# PEAK_LCW_1.net
KiCad netlist of a schematic drawn in Altium Designer
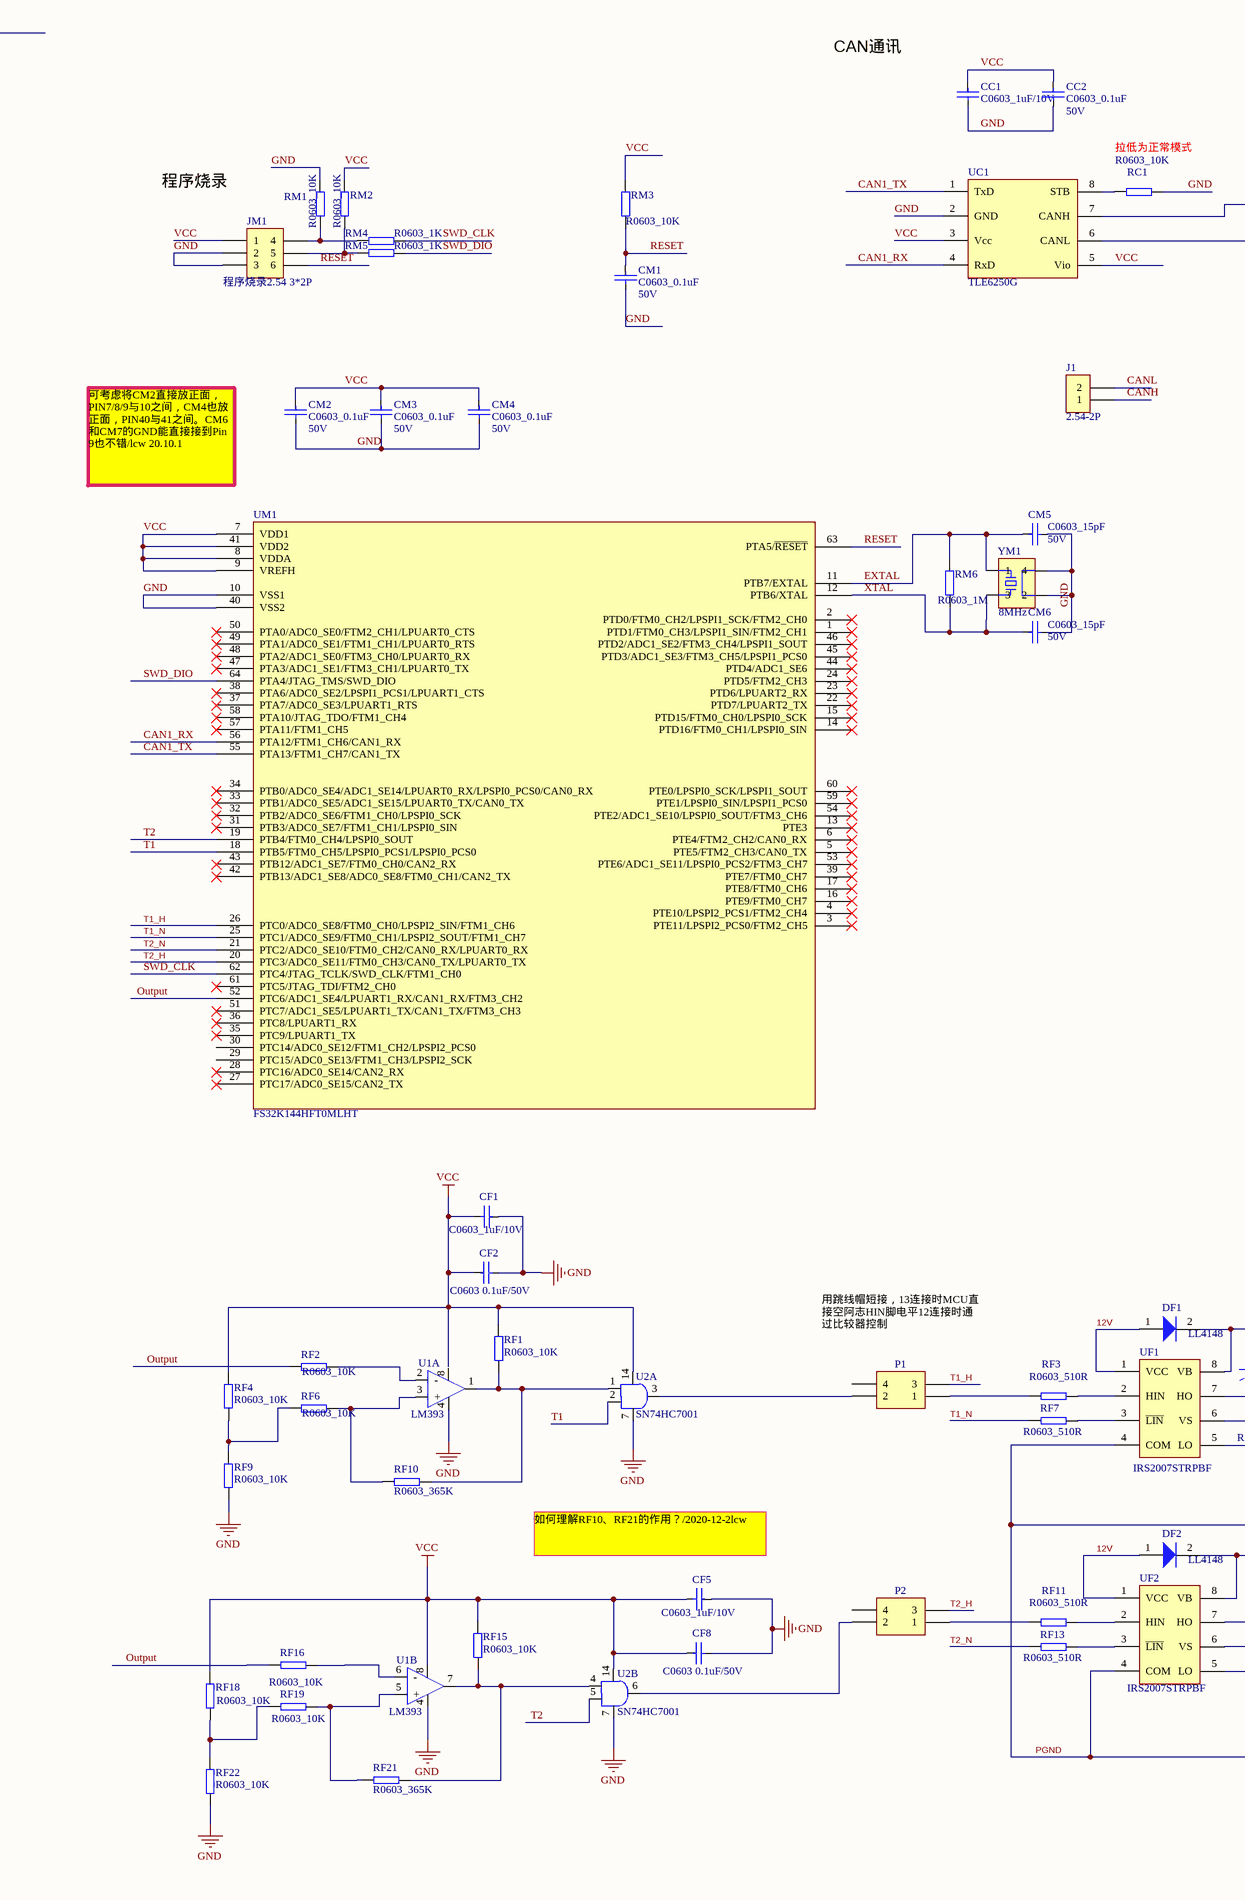
[diagram p0: PEAK——LCW (1).SchDoc, left]
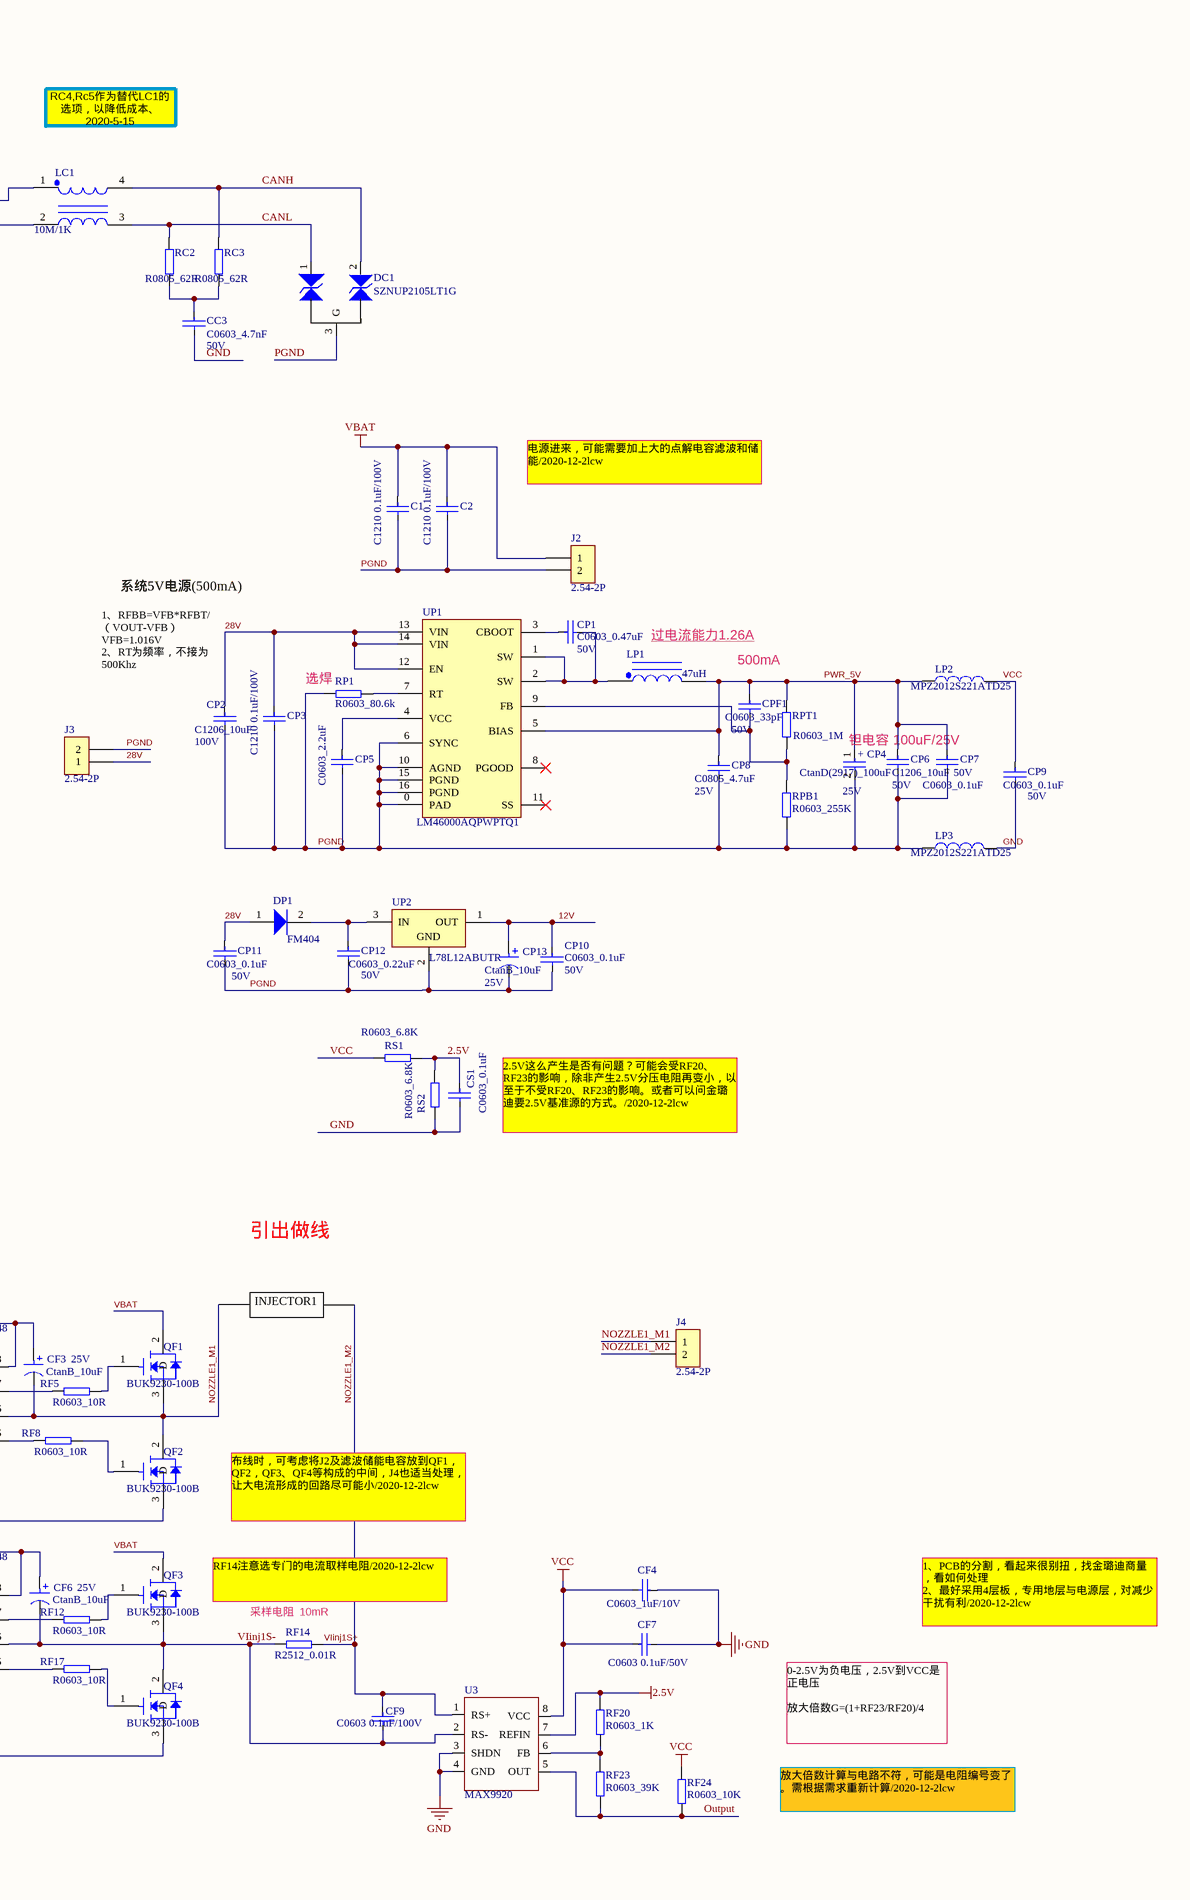
[diagram p1: PEAK——LCW (1).SchDoc, right]

(export (version "E")
  (design (tool "Eeschema 10.0.6"))
  (components
    (comp (ref "C1")
      (value "C1210 0.1uF/100V")
      (footprint "C1210")
      (description "C1210 0.1uF/50V 10%")
      (fields (field (name "VOLTAGE") "100V") (field (name "PART NUMBER") "3170014005"))
      (libsource (lib "BMSer") (part "CAP"))
    )
    (comp (ref "C2")
      (value "C1210 0.1uF/100V")
      (footprint "C1210")
      (description "C1210 0.1uF/50V 10%")
      (fields (field (name "VOLTAGE") "100V") (field (name "PART NUMBER") "3170014005"))
      (libsource (lib "BMSer") (part "CAP"))
    )
    (comp (ref "CC1")
      (value "C0603_1uF/10V")
      (footprint "C0603")
      (description "C0603 0.1uF/50V 10%")
      (fields (field (name "VOLTAGE") "10V") (field (name "PART NUMBER") "3170011015"))
      (libsource (lib "BMSer") (part "CAP"))
    )
    (comp (ref "CC2")
      (value "C0603_0.1uF")
      (footprint "C0603")
      (description "C0603 0.1uF/50V 10%")
      (fields
        (field (name "VOLTAGE") "50V")
        (field (name "PART NUMBER") "3170011015")
        (field (name "MANUFACTURER") "YAGEO")
      )
      (libsource (lib "BMSer") (part "CAP"))
    )
    (comp (ref "CC3")
      (value "C0603_4.7nF")
      (footprint "C0603")
      (description "C0603 4.7nF/50V 5% X7R")
      (fields
        (field (name "VOLTAGE") "50V")
        (field (name "PART NUMBER") "3170011009")
        (field (name "MANUFACTURER") "YAGEO")
      )
      (libsource (lib "BMSer") (part "CAP"))
    )
    (comp (ref "CF1")
      (value "C0603_1uF/10V")
      (footprint "C0603")
      (description "C0603 0.1uF/50V 10%")
      (fields (field (name "VOLTAGE") "10V") (field (name "PART NUMBER") "3170011015"))
      (libsource (lib "BMSer") (part "CAP"))
    )
    (comp (ref "CF2")
      (value "C0603 0.1uF/50V")
      (footprint "C0603")
      (description "C0603 0.1uF/50V 10%")
      (fields (field (name "VOLTAGE") "50V") (field (name "PART NUMBER") "3170011015"))
      (libsource (lib "BMSer") (part "CAP"))
    )
    (comp (ref "CF3")
      (value "CtanB_10uF")
      (footprint "CTANB")
      (description "CtanB(1210) 10uF/25V 10%")
      (fields
        (field (name "PART NUMBER") "3172690034")
        (field (name "MANUFACTURER") "AVX")
        (field (name "VOLTAGE") "25V")
      )
      (libsource (lib "BMSer") (part "CAP_T"))
    )
    (comp (ref "CF4")
      (value "C0603_1uF/10V")
      (footprint "C0603")
      (description "C0603 0.1uF/50V 10%")
      (fields (field (name "VOLTAGE") "10V") (field (name "PART NUMBER") "3170011015"))
      (libsource (lib "BMSer") (part "CAP"))
    )
    (comp (ref "CF5")
      (value "C0603_1uF/10V")
      (footprint "C0603")
      (description "C0603 0.1uF/50V 10%")
      (fields (field (name "VOLTAGE") "10V") (field (name "PART NUMBER") "3170011015"))
      (libsource (lib "BMSer") (part "CAP"))
    )
    (comp (ref "CF6")
      (value "CtanB_10uF")
      (footprint "CTANB")
      (description "CtanB(1210) 10uF/25V 10%")
      (fields
        (field (name "PART NUMBER") "3172690034")
        (field (name "MANUFACTURER") "AVX")
        (field (name "VOLTAGE") "25V")
      )
      (libsource (lib "BMSer") (part "CAP_T"))
    )
    (comp (ref "CF7")
      (value "C0603 0.1uF/50V")
      (footprint "C0603")
      (description "C0603 0.1uF/50V 10%")
      (fields (field (name "VOLTAGE") "50V") (field (name "PART NUMBER") "3170011015"))
      (libsource (lib "BMSer") (part "CAP"))
    )
    (comp (ref "CF8")
      (value "C0603 0.1uF/50V")
      (footprint "C0603")
      (description "C0603 0.1uF/50V 10%")
      (fields (field (name "VOLTAGE") "50V") (field (name "PART NUMBER") "3170011015"))
      (libsource (lib "BMSer") (part "CAP"))
    )
    (comp (ref "CF9")
      (value "C0603 0.1uF/100V")
      (footprint "C0603")
      (description "C0603 0.1uF/50V 10%")
      (fields (field (name "VOLTAGE") "50V") (field (name "PART NUMBER") "3170011015"))
      (libsource (lib "BMSer") (part "CAP"))
    )
    (comp (ref "CM1")
      (value "C0603_0.1uF")
      (footprint "C0603")
      (description "C0603 0.1uF/50V 10%")
      (fields
        (field (name "VOLTAGE") "50V")
        (field (name "PART NUMBER") "3170011015")
        (field (name "MANUFACTURER") "YAGEO")
      )
      (libsource (lib "BMSer") (part "CAP"))
    )
    (comp (ref "CM2")
      (value "C0603_0.1uF")
      (footprint "C0603")
      (description "C0603 0.1uF/50V 10%")
      (fields
        (field (name "VOLTAGE") "50V")
        (field (name "PART NUMBER") "3170011015")
        (field (name "MANUFACTURER") "YAGEO")
      )
      (libsource (lib "BMSer") (part "CAP"))
    )
    (comp (ref "CM3")
      (value "C0603_0.1uF")
      (footprint "C0603")
      (description "C0603 0.1uF/50V 10%")
      (fields
        (field (name "VOLTAGE") "50V")
        (field (name "PART NUMBER") "3170011015")
        (field (name "MANUFACTURER") "YAGEO")
      )
      (libsource (lib "BMSer") (part "CAP"))
    )
    (comp (ref "CM4")
      (value "C0603_0.1uF")
      (footprint "C0603")
      (description "C0603 0.1uF/50V 10%")
      (fields
        (field (name "VOLTAGE") "50V")
        (field (name "PART NUMBER") "3170011015")
        (field (name "MANUFACTURER") "YAGEO")
      )
      (libsource (lib "BMSer") (part "CAP"))
    )
    (comp (ref "CM5")
      (value "C0603_15pF")
      (footprint "C0603")
      (description "C0603 15pF/50V 10%")
      (fields
        (field (name "VOLTAGE") "50V")
        (field (name "PART NUMBER") "3172510040")
        (field (name "MANUFACTURER") "YAGEO")
      )
      (libsource (lib "BMSer") (part "CAP"))
    )
    (comp (ref "CM6")
      (value "C0603_15pF")
      (footprint "C0603")
      (description "C0603 15pF/50V 10%")
      (fields
        (field (name "VOLTAGE") "50V")
        (field (name "PART NUMBER") "3172510040")
        (field (name "MANUFACTURER") "YAGEO")
      )
      (libsource (lib "BMSer") (part "CAP"))
    )
    (comp (ref "CP1")
      (value "C0603_0.47uF")
      (footprint "C0603")
      (description "C0603 0.47uF/50V 10%")
      (fields
        (field (name "VOLTAGE") "50V")
        (field (name "PART NUMBER") "3170011017")
        (field (name "MANUFACTURER") "murata")
      )
      (libsource (lib "BMSer") (part "CAP"))
    )
    (comp (ref "CP2")
      (value "C1206_10uF")
      (footprint "C1206")
      (description "C1206 10uF/50V  10%")
      (fields
        (field (name "VOLTAGE") "100V")
        (field (name "PART NUMBER") "3172530019")
        (field (name "MANUFACTURER") "YAGEO")
      )
      (libsource (lib "BMSer") (part "CAP"))
    )
    (comp (ref "CP3")
      (value "C1210 0.1uF/100V")
      (footprint "C1210")
      (description "C1210 0.1uF/100V 10%")
      (fields (field (name "VOLTAGE") "100V") (field (name "PART NUMBER") "3170014005"))
      (libsource (lib "BMSer") (part "CAP"))
    )
    (comp (ref "CP4")
      (value "CtanD(2917)_100uF")
      (footprint "CTAND")
      (description "CtanD(2917) 100uF/25V 10%")
      (fields
        (field (name "VOLTAGE") "25V")
        (field (name "PART NUMBER") "3170030004")
        (field (name "MANUFACTURER") "AVX")
      )
      (libsource (lib "BMSer") (part "CAP_E"))
    )
    (comp (ref "CP5")
      (value "C0603_2.2uF")
      (footprint "C0603")
      (description "C0603 2.2uF/50V 10%")
      (fields (field (name "VOLTAGE") "50V") (field (name "PART NUMBER") "3170011030"))
      (libsource (lib "BMSer") (part "CAP"))
    )
    (comp (ref "CP6")
      (value "C1206_10uF")
      (footprint "C1206")
      (description "C1206 10uF/50V  10%")
      (fields
        (field (name "VOLTAGE") "50V")
        (field (name "PART NUMBER") "3172530019")
        (field (name "MANUFACTURER") "YAGEO")
      )
      (libsource (lib "BMSer") (part "CAP"))
    )
    (comp (ref "CP7")
      (value "C0603_0.1uF")
      (footprint "C0603")
      (description "C0603 0.1uF/50V 10%")
      (fields
        (field (name "VOLTAGE") "50V")
        (field (name "PART NUMBER") "3170011015")
        (field (name "MANUFACTURER") "YAGEO")
      )
      (libsource (lib "BMSer") (part "CAP"))
    )
    (comp (ref "CP8")
      (value "C0805_4.7uF")
      (footprint "C0805")
      (description "C0805 4.7uF/25V 10%")
      (fields
        (field (name "VOLTAGE") "25V")
        (field (name "PART NUMBER") "3170012010")
        (field (name "MANUFACTURER") "YAGEO")
      )
      (libsource (lib "BMSer") (part "CAP"))
    )
    (comp (ref "CP9")
      (value "C0603_0.1uF")
      (footprint "C0603")
      (description "C0603 0.1uF/50V 10%")
      (fields
        (field (name "VOLTAGE") "50V")
        (field (name "PART NUMBER") "3170011015")
        (field (name "MANUFACTURER") "YAGEO")
      )
      (libsource (lib "BMSer") (part "CAP"))
    )
    (comp (ref "CP10")
      (value "C0603_0.1uF")
      (footprint "C0603")
      (description "C0603 0.1uF/50V 10%  X7R")
      (fields
        (field (name "VOLTAGE") "50V")
        (field (name "PART NUMBER") "3170011015")
        (field (name "MANUFACTURER") "YAGEO")
      )
      (libsource (lib "BMSer") (part "CAP"))
    )
    (comp (ref "CP11")
      (value "C0603_0.1uF")
      (footprint "C0603")
      (description "C0603 0.1uF/50V 10%")
      (fields
        (field (name "VOLTAGE") "50V")
        (field (name "PART NUMBER") "3170011015")
        (field (name "MANUFACTURER") "YAGEO")
      )
      (libsource (lib "BMSer") (part "CAP"))
    )
    (comp (ref "CP12")
      (value "C0603_0.22uF")
      (footprint "C0603")
      (description "C0603 0.22uF/50V 10%")
      (fields
        (field (name "VOLTAGE") "50V")
        (field (name "PART NUMBER") "3172510028")
        (field (name "MANUFACTURER") "YAGEO")
      )
      (libsource (lib "BMSer") (part "CAP"))
    )
    (comp (ref "CP13")
      (value "CtanB_10uF")
      (footprint "CTANB")
      (description "CtanB(1210) 10uF/25V 10%")
      (fields
        (field (name "PART NUMBER") "3172690034")
        (field (name "MANUFACTURER") "AVX")
        (field (name "VOLTAGE") "25V")
      )
      (libsource (lib "BMSer") (part "CAP_T"))
    )
    (comp (ref "CPF1")
      (value "C0603_33pF")
      (footprint "C0603")
      (description "C0603 33pF/50V 10%")
      (fields
        (field (name "VOLTAGE") "50V")
        (field (name "PART NUMBER") "3172510041")
        (field (name "MANUFACTURER") "YAGEO")
      )
      (libsource (lib "BMSer") (part "CAP"))
    )
    (comp (ref "CS1")
      (value "C0603_0.1uF")
      (footprint "C0603")
      (description "C0603 0.1uF/50V 10%")
      (fields (field (name "VOLTAGE") "50V") (field (name "PART NUMBER") "3170011015"))
      (libsource (lib "BMSer") (part "CAP"))
    )
    (comp (ref "DC1")
      (value "SZNUP2105LT1G")
      (footprint "SOT-23")
      (description "SOT-23 SZNUP2105LT1G")
      (fields (field (name "PART NUMBER") "3110050073") (field (name "MANUFACTURER") "ON"))
      (libsource (lib "BMSer") (part "SZNUP2105LT1G"))
    )
    (comp (ref "DF1")
      (value "LL4148")
      (footprint "SOD-80")
      (description "SOD-80  LL4148 2A/75V")
      (fields (field (name "PART NUMBER") "3110010015") (field (name "MANUFACTURER") "VISHA"))
      (libsource (lib "BMSer") (part "DIODE"))
    )
    (comp (ref "DF2")
      (value "LL4148")
      (footprint "SOD-80")
      (description "SOD-80  LL4148 2A/75V")
      (fields (field (name "PART NUMBER") "3110010015") (field (name "MANUFACTURER") "VISHA"))
      (libsource (lib "BMSer") (part "DIODE"))
    )
    (comp (ref "DP1")
      (value "FM404")
      (footprint "D0-214AC")
      (description "D0-214AC FM404")
      (fields (field (name "PART NUMBER") "13110010013") (field (name "MANUFACTURER") "LRC"))
      (libsource (lib "BMSer") (part "DIODE"))
    )
    (comp (ref "J1")
      (value "2.54-2P")
      (footprint "2.54-2P")
      (fields (field (name "PART NUMBER") "53190010200"))
      (libsource (lib "BMSer") (part "CON2"))
    )
    (comp (ref "J2")
      (value "2.54-2P")
      (footprint "2.54-2P")
      (fields (field (name "PART NUMBER") "53190010200"))
      (libsource (lib "") (part "CON2_1"))
    )
    (comp (ref "J3")
      (value "2.54-2P")
      (footprint "2.54-2P")
      (fields (field (name "PART NUMBER") "53190010200"))
      (libsource (lib "BMSer") (part "CON2"))
    )
    (comp (ref "J4")
      (value "2.54-2P")
      (footprint "2.54-2P")
      (fields (field (name "PART NUMBER") "53190010200"))
      (libsource (lib "") (part "CON2_1"))
    )
    (comp (ref "JM1")
      (value "程序烧录2.54 3*2P")
      (footprint "3x2P")
      (fields (field (name "PART NUMBER") "53190010221"))
      (libsource (lib "BMSer") (part "CON3x2"))
    )
    (comp (ref "LC1")
      (value "10M/1K")
      (footprint "ACT45B")
      (description "ACT45B-510-2P-TL  10M/1K/0.2A")
      (fields (field (name "PART NUMBER") "3180020022") (field (name "MANUFACTURER") "TDK"))
      (libsource (lib "BMSer") (part "INDUCTOR3"))
    )
    (comp (ref "LP1")
      (value "47uH")
      (footprint "LGK")
      (description "CLF7045NIT-470M-D  47uH/1.26A  Q")
      (fields (field (name "PART NUMBER") "53180020033") (field (name "MANUFACTURER") "TDK"))
      (libsource (lib "BMSer") (part "INDUCTOR2"))
    )
    (comp (ref "LP2")
      (value "MPZ2012S221ATD25")
      (footprint "L 0805")
      (description "L0805 MPZ2012S221ATD25")
      (fields (field (name "PART NUMBER") "53180020011") (field (name "MANUFACTURER") "TDK"))
      (libsource (lib "BMSer") (part "INDUCTOR1"))
    )
    (comp (ref "LP3")
      (value "MPZ2012S221ATD25")
      (footprint "L 0805")
      (description "L0805 MPZ2012S221ATD25")
      (fields (field (name "PART NUMBER") "53180020011") (field (name "MANUFACTURER") "TDK"))
      (libsource (lib "BMSer") (part "INDUCTOR1"))
    )
    (comp (ref "P1")
      (value "Header 2X2")
      (footprint "HDR2X2")
      (description "Header, 2-Pin, Dual row")
      (fields (field (name "PUBLISHER") "Altium Limited"))
      (libsource (lib "Miscellaneous Connectors") (part "Header 2X2"))
    )
    (comp (ref "P2")
      (value "Header 2X2")
      (footprint "HDR2X2")
      (description "Header, 2-Pin, Dual row")
      (fields (field (name "PUBLISHER") "Altium Limited"))
      (libsource (lib "Miscellaneous Connectors") (part "Header 2X2"))
    )
    (comp (ref "QF1")
      (value "BUK9230-100B")
      (footprint "DPAK-3_L6.6-W6.1-P2.28-LS9.9-BR")
      (description "TO-252-3 FDD86567-F085 60V/100A")
      (fields (field (name "PART NUMBER") "53110022012") (field (name "MANUFACTURER") "ON"))
      (libsource (lib "BMSer") (part "NMOSGDS"))
    )
    (comp (ref "QF2")
      (value "BUK9230-100B")
      (footprint "DPAK-3_L6.6-W6.1-P2.28-LS9.9-BR")
      (description "TO-252-3 FDD86567-F085 60V/100A")
      (fields (field (name "PART NUMBER") "53110022012") (field (name "MANUFACTURER") "ON"))
      (libsource (lib "BMSer") (part "NMOSGDS"))
    )
    (comp (ref "QF3")
      (value "BUK9230-100B")
      (footprint "DPAK-3_L6.6-W6.1-P2.28-LS9.9-BR")
      (description "TO-252-3 FDD86567-F085 60V/100A")
      (fields (field (name "PART NUMBER") "53110022012") (field (name "MANUFACTURER") "ON"))
      (libsource (lib "BMSer") (part "NMOSGDS"))
    )
    (comp (ref "QF4")
      (value "BUK9230-100B")
      (footprint "DPAK-3_L6.6-W6.1-P2.28-LS9.9-BR")
      (description "TO-252-3 FDD86567-F085 60V/100A")
      (fields (field (name "PART NUMBER") "53110022012") (field (name "MANUFACTURER") "ON"))
      (libsource (lib "BMSer") (part "NMOSGDS"))
    )
    (comp (ref "RC1")
      (value "R0603_10K")
      (footprint "R0603")
      (description "R0603 1/10w 10K 1%")
      (fields (field (name "PART NUMBER") "3160030053") (field (name "MANUFACTURER") "YAGEO"))
      (libsource (lib "BMSer") (part "RS"))
    )
    (comp (ref "RC2")
      (value "R0805_62R")
      (footprint "R0805")
      (description "R0805 1/8w10R 1%")
      (fields (field (name "PART NUMBER") "3160050016") (field (name "MANUFACTURER") "YAGEO"))
      (libsource (lib "BMSer") (part "RS"))
    )
    (comp (ref "RC3")
      (value "R0805_62R")
      (footprint "R0805")
      (description "R0805 1/8w10R 1%")
      (fields (field (name "PART NUMBER") "3160050016") (field (name "MANUFACTURER") "YAGEO"))
      (libsource (lib "BMSer") (part "RS"))
    )
    (comp (ref "RF1")
      (value "R0603_10K")
      (footprint "R0603")
      (description "R0603 1/10w 10K 1%")
      (fields (field (name "PART NUMBER") "3160030053") (field (name "MANUFACTURER") "YAGEO"))
      (libsource (lib "BMSer") (part "RS"))
    )
    (comp (ref "RF2")
      (value "R0603_10K")
      (footprint "R0603")
      (description "R0603 1/10w 10K 1%")
      (fields (field (name "PART NUMBER") "3160030053") (field (name "MANUFACTURER") "YAGEO"))
      (libsource (lib "BMSer") (part "RS"))
    )
    (comp (ref "RF3")
      (value "R0603_510R")
      (footprint "R0603")
      (description "R0603  1/10w 510R 1%")
      (fields (field (name "PART NUMBER") "3160030020") (field (name "MANUFACTURER") "YAGEO"))
      (libsource (lib "BMSer") (part "RS"))
    )
    (comp (ref "RF4")
      (value "R0603_10K")
      (footprint "R0603")
      (description "R0603 1/10w 10K 1%")
      (fields (field (name "PART NUMBER") "3160030053") (field (name "MANUFACTURER") "YAGEO"))
      (libsource (lib "BMSer") (part "RS"))
    )
    (comp (ref "RF5")
      (value "R0603_10R")
      (footprint "R0603")
      (description "R0603 1/10w  10R 1%")
      (fields (field (name "PART NUMBER") "3160030193") (field (name "MANUFACTURER") "YAGEO"))
      (libsource (lib "BMSer") (part "RS"))
    )
    (comp (ref "RF6")
      (value "R0603_10K")
      (footprint "R0603")
      (description "R0603 1/10w 10K 1%")
      (fields (field (name "PART NUMBER") "3160030053") (field (name "MANUFACTURER") "YAGEO"))
      (libsource (lib "BMSer") (part "RS"))
    )
    (comp (ref "RF7")
      (value "R0603_510R")
      (footprint "R0603")
      (description "R0603  1/10w 510R 1%")
      (fields (field (name "PART NUMBER") "3160030020") (field (name "MANUFACTURER") "YAGEO"))
      (libsource (lib "BMSer") (part "RS"))
    )
    (comp (ref "RF8")
      (value "R0603_10R")
      (footprint "R0603")
      (description "R0603 1/10w  10R 1%")
      (fields (field (name "PART NUMBER") "3160030193") (field (name "MANUFACTURER") "YAGEO"))
      (libsource (lib "BMSer") (part "RS"))
    )
    (comp (ref "RF9")
      (value "R0603_10K")
      (footprint "R0603")
      (description "R0603 1/10w 10K 1%")
      (fields (field (name "PART NUMBER") "3160030053") (field (name "MANUFACTURER") "YAGEO"))
      (libsource (lib "BMSer") (part "RS"))
    )
    (comp (ref "RF10")
      (value "R0603_365K")
      (footprint "R0603")
      (description "R0603 1/10w 365K 1%")
      (fields (field (name "PART NUMBER") "3160030166") (field (name "MANUFACTURER") "YAGEO"))
      (libsource (lib "BMSer") (part "RS"))
    )
    (comp (ref "RF11")
      (value "R0603_510R")
      (footprint "R0603")
      (description "R0603  1/10w 510R 1%")
      (fields (field (name "PART NUMBER") "3160030020") (field (name "MANUFACTURER") "YAGEO"))
      (libsource (lib "BMSer") (part "RS"))
    )
    (comp (ref "RF12")
      (value "R0603_10R")
      (footprint "R0603")
      (description "R0603 1/10w  10R 1%")
      (fields (field (name "PART NUMBER") "3160030193") (field (name "MANUFACTURER") "YAGEO"))
      (libsource (lib "BMSer") (part "RS"))
    )
    (comp (ref "RF13")
      (value "R0603_510R")
      (footprint "R0603")
      (description "R0603  1/10w 510R 1%")
      (fields (field (name "PART NUMBER") "3160030020") (field (name "MANUFACTURER") "YAGEO"))
      (libsource (lib "BMSer") (part "RS"))
    )
    (comp (ref "RF14")
      (value "R2512_0.01R")
      (footprint "R2512")
      (description "R2512 1W 0.01R 1%")
      (fields (field (name "PART NUMBER") "3162380033") (field (name "MANUFACTURER") "YAGEO"))
      (libsource (lib "BMSer") (part "RS"))
    )
    (comp (ref "RF15")
      (value "R0603_10K")
      (footprint "R0603")
      (description "R0603 1/10w 10K 1%")
      (fields (field (name "PART NUMBER") "3160030053") (field (name "MANUFACTURER") "YAGEO"))
      (libsource (lib "BMSer") (part "RS"))
    )
    (comp (ref "RF16")
      (value "R0603_10K")
      (footprint "R0603")
      (description "R0603 1/10w 10K 1%")
      (fields (field (name "PART NUMBER") "3160030053") (field (name "MANUFACTURER") "YAGEO"))
      (libsource (lib "BMSer") (part "RS"))
    )
    (comp (ref "RF17")
      (value "R0603_10R")
      (footprint "R0603")
      (description "R0603 1/10w  10R 1%")
      (fields (field (name "PART NUMBER") "3160030193") (field (name "MANUFACTURER") "YAGEO"))
      (libsource (lib "BMSer") (part "RS"))
    )
    (comp (ref "RF18")
      (value "R0603_10K")
      (footprint "R0603")
      (description "R0603 1/10w 10K 1%")
      (fields (field (name "PART NUMBER") "3160030053") (field (name "MANUFACTURER") "YAGEO"))
      (libsource (lib "BMSer") (part "RS"))
    )
    (comp (ref "RF19")
      (value "R0603_10K")
      (footprint "R0603")
      (description "R0603 1/10w 10K 1%")
      (fields (field (name "PART NUMBER") "3160030053") (field (name "MANUFACTURER") "YAGEO"))
      (libsource (lib "BMSer") (part "RS"))
    )
    (comp (ref "RF20")
      (value "R0603_1K")
      (footprint "R0603")
      (description "R0603  1/10w 1K 1%")
      (fields (field (name "PART NUMBER") "3160030021") (field (name "MANUFACTURER") "YAGEO"))
      (libsource (lib "BMSer") (part "RS"))
    )
    (comp (ref "RF21")
      (value "R0603_365K")
      (footprint "R0603")
      (description "R0603 1/10w 365K 1%")
      (fields (field (name "PART NUMBER") "3160030166") (field (name "MANUFACTURER") "YAGEO"))
      (libsource (lib "BMSer") (part "RS"))
    )
    (comp (ref "RF22")
      (value "R0603_10K")
      (footprint "R0603")
      (description "R0603 1/10w 10K 1%")
      (fields (field (name "PART NUMBER") "3160030053") (field (name "MANUFACTURER") "YAGEO"))
      (libsource (lib "BMSer") (part "RS"))
    )
    (comp (ref "RF23")
      (value "R0603_39K")
      (footprint "R0603")
      (description "R0603 1/10w 39K 1%")
      (fields (field (name "PART NUMBER") "3160030165") (field (name "MANUFACTURER") "YAGEO/UNIOHM"))
      (libsource (lib "BMSer") (part "RS"))
    )
    (comp (ref "RF24")
      (value "R0603_10K")
      (footprint "R0603")
      (description "R0603 1/10w 10K 1%")
      (fields (field (name "PART NUMBER") "3160030053") (field (name "MANUFACTURER") "YAGEO"))
      (libsource (lib "BMSer") (part "RS"))
    )
    (comp (ref "RM1")
      (value "R0603_10K")
      (footprint "R0603")
      (description "R0603 1/10w 10K 1%")
      (fields (field (name "PART NUMBER") "3160030053") (field (name "MANUFACTURER") "YAGEO"))
      (libsource (lib "BMSer") (part "RS"))
    )
    (comp (ref "RM2")
      (value "R0603_10K")
      (footprint "R0603")
      (description "R0603 1/10w 10K 1%")
      (fields (field (name "PART NUMBER") "3160030053") (field (name "MANUFACTURER") "YAGEO"))
      (libsource (lib "BMSer") (part "RS"))
    )
    (comp (ref "RM3")
      (value "R0603_10K")
      (footprint "R0603")
      (description "R0603 1/10w 10K 1%")
      (fields (field (name "PART NUMBER") "3160030053") (field (name "MANUFACTURER") "YAGEO"))
      (libsource (lib "BMSer") (part "RS"))
    )
    (comp (ref "RM4")
      (value "R0603_1K")
      (footprint "R0603")
      (description "R0603  1/10w 1K 1%")
      (fields (field (name "PART NUMBER") "3160030021") (field (name "MANUFACTURER") "YAGEO"))
      (libsource (lib "BMSer") (part "RS"))
    )
    (comp (ref "RM5")
      (value "R0603_1K")
      (footprint "R0603")
      (description "R0603  1/10w 1K 1%")
      (fields (field (name "PART NUMBER") "3160030021") (field (name "MANUFACTURER") "YAGEO"))
      (libsource (lib "BMSer") (part "RS"))
    )
    (comp (ref "RM6")
      (value "R0603_1M")
      (footprint "R0603")
      (description "R0603 1/10w 1M 1%")
      (fields (field (name "PART NUMBER") "3160030183") (field (name "MANUFACTURER") "YAGEO/UNIOHM"))
      (libsource (lib "BMSer") (part "RS"))
    )
    (comp (ref "RP1")
      (value "R0603_80.6k")
      (footprint "R0603")
      (description "R0603 1/10w 80.6k 1%")
      (fields (field (name "PART NUMBER") "3162310230") (field (name "MANUFACTURER") "YAGEO"))
      (libsource (lib "BMSer") (part "RS"))
    )
    (comp (ref "RPB1")
      (value "R0603_255K")
      (footprint "R0603")
      (description "R0603 1/10w255K 1%")
      (fields (field (name "PART NUMBER") "3160030153") (field (name "MANUFACTURER") "YAGEO"))
      (libsource (lib "BMSer") (part "RS"))
    )
    (comp (ref "RPT1")
      (value "R0603_1M")
      (footprint "R0603")
      (description "R0603 1/10w 1M 1%")
      (fields (field (name "PART NUMBER") "3160030183") (field (name "MANUFACTURER") "YAGEO/UNIOHM"))
      (libsource (lib "BMSer") (part "RS"))
    )
    (comp (ref "RS1")
      (value "R0603_6.8K")
      (footprint "R0603")
      (description "R0603 1/10w 6.8K")
      (fields (field (name "PART NUMBER") "3160030047") (field (name "MANUFACTURER") "YAGEO"))
      (libsource (lib "BMSer") (part "RS"))
    )
    (comp (ref "RS2")
      (value "R0603_6.8K")
      (footprint "R0603")
      (description "R0603  1/10w 2.4K")
      (fields (field (name "PART NUMBER") "3160030031") (field (name "MANUFACTURER") "YAGEO"))
      (libsource (lib "BMSer") (part "RS"))
    )
    (comp (ref "U1")
      (value "LM393")
      (footprint "SOIC-8_L5.0-W4.0-P1.27-LS6.0-BL")
      (libsource (lib "Schlib1") (part "LM393"))
    )
    (comp (ref "U2")
      (value "SN74HC7001")
      (footprint "SOIC-14_L8.7-W3.9-P1.27-LS6.0-BL")
      (libsource (lib "Schlib1") (part "SN74HC7001"))
    )
    (comp (ref "U3")
      (value "MAX9920")
      (footprint "SOIC-8_L5.0-W4.0-P1.27-LS6.0-BL")
      (libsource (lib "Schlib1") (part "MAX9920"))
    )
    (comp (ref "UC1")
      (value "TLE6250G")
      (footprint "PG-DSO-8")
      (description "PG-DSO-8 TLE9251VSJ")
      (fields (field (name "PART NUMBER") "3100050124") (field (name "MANUFACTURER") "infineon"))
      (libsource (lib "BMSer") (part "TLE9251VSJ"))
    )
    (comp (ref "UF1")
      (value "IRS2007STRPBF")
      (footprint "SOIC-8L")
      (description "SOIC-8L IRS2007STRPBF")
      (fields (field (name "PART NUMBER") "3100050121") (field (name "MANUFACTURER") "infineon"))
      (libsource (lib "BMSer") (part "IRS2007STRPBF"))
    )
    (comp (ref "UF2")
      (value "IRS2007STRPBF")
      (footprint "SOIC-8L")
      (description "SOIC-8L IRS2007STRPBF")
      (fields (field (name "PART NUMBER") "3100050121") (field (name "MANUFACTURER") "infineon"))
      (libsource (lib "BMSer") (part "IRS2007STRPBF"))
    )
    (comp (ref "UM1")
      (value "FS32K144HFT0MLHT")
      (footprint "LQFP-64")
      (description "LQFP-64 FS32K144HFT0MLHT")
      (fields (field (name "PART NUMBER") "3100010021") (field (name "MANUFACTURER") "NXP"))
      (libsource (lib "BMSer") (part "FS32K144HFT0MLHT"))
    )
    (comp (ref "UP1")
      (value "LM46000AQPWPTQ1")
      (footprint "HTSSOP-16")
      (description "HTSSOP-16 LM46000AQPWPTQ1 60V/0.5A降压  Q")
      (fields (field (name "PART NUMBER") "3100050127") (field (name "MANUFACTURER") "TI"))
      (libsource (lib "BMSer") (part "LM46000AQPWPTQ1"))
    )
    (comp (ref "UP2")
      (value "L78L12ABUTR")
      (footprint "SOT-89")
      (description "SOT-89 L78L12ABUTR")
      (fields (field (name "PART NUMBER") "3100050105") (field (name "MANUFACTURER") "ST"))
      (libsource (lib "BMSer") (part "L78L12ABUTR"))
    )
    (comp (ref "YM1")
      (value "8MHz")
      (footprint "5.0*3.2_4")
      (description "5.0*3.2  8MHz 15pF")
      (fields (field (name "PART NUMBER") "53120010026") (field (name "MANUFACTURER") "HKC"))
      (libsource (lib "BMSer") (part "XTAL_4"))
    )
  )
  (nets
    (net (code "1") (name "/12V") (class "Default")
      (node (ref "CP10") (pin "1") (pintype "passive"))
      (node (ref "CP13") (pin "1") (pinfunction "1_1") (pintype "passive"))
      (node (ref "DF1") (pin "1") (pinfunction "1_1") (pintype "passive"))
      (node (ref "DF2") (pin "1") (pinfunction "1_1") (pintype "passive"))
      (node (ref "UF1") (pin "1") (pinfunction "VCC_1") (pintype "passive"))
      (node (ref "UF2") (pin "1") (pinfunction "VCC_1") (pintype "passive"))
      (node (ref "UP2") (pin "1") (pinfunction "OUT_1") (pintype "passive"))
    )
    (net (code "2") (name "/28V") (class "Default")
      (node (ref "CP11") (pin "1") (pintype "passive"))
      (node (ref "CP2") (pin "1") (pintype "passive"))
      (node (ref "CP3") (pin "1") (pintype "passive"))
      (node (ref "DP1") (pin "1") (pinfunction "1_1") (pintype "passive"))
      (node (ref "J3") (pin "1") (pinfunction "1_1") (pintype "passive"))
      (node (ref "UP1") (pin "12") (pinfunction "EN_12") (pintype "passive"))
      (node (ref "UP1") (pin "13") (pinfunction "VIN_13") (pintype "passive"))
      (node (ref "UP1") (pin "14") (pinfunction "VIN_14") (pintype "passive"))
    )
    (net (code "3") (name "/CAN1_RX") (class "Default")
      (node (ref "UC1") (pin "4") (pinfunction "RxD_4") (pintype "passive"))
      (node (ref "UM1") (pin "56") (pinfunction "PTA12/FTM1_CH6/CAN1_RX_56") (pintype "passive"))
    )
    (net (code "4") (name "/CAN1_TX") (class "Default")
      (node (ref "UC1") (pin "1") (pinfunction "TxD_1") (pintype "passive"))
      (node (ref "UM1") (pin "55") (pinfunction "PTA13/FTM1_CH7/CAN1_TX_55") (pintype "passive"))
    )
    (net (code "5") (name "/CANH") (class "Default")
      (node (ref "DC1") (pin "2") (pinfunction "2_2") (pintype "passive"))
      (node (ref "J1") (pin "1") (pinfunction "1_1") (pintype "passive"))
      (node (ref "LC1") (pin "4") (pinfunction "4_4") (pintype "passive"))
      (node (ref "RC3") (pin "2") (pintype "passive"))
    )
    (net (code "6") (name "/CANL") (class "Default")
      (node (ref "DC1") (pin "1") (pinfunction "1_1") (pintype "passive"))
      (node (ref "J1") (pin "2") (pinfunction "2_2") (pintype "passive"))
      (node (ref "LC1") (pin "3") (pinfunction "3_3") (pintype "passive"))
      (node (ref "RC2") (pin "2") (pintype "passive"))
    )
    (net (code "7") (name "/EXTAL") (class "Default")
      (node (ref "CM5") (pin "1") (pintype "passive"))
      (node (ref "RM6") (pin "2") (pintype "passive"))
      (node (ref "UM1") (pin "11") (pinfunction "PTB7/EXTAL_11") (pintype "passive"))
      (node (ref "YM1") (pin "1") (pinfunction "1_1") (pintype "passive"))
    )
    (net (code "8") (name "/NOZZLE1_M1") (class "Default")
      (node (ref "CF3") (pin "2") (pinfunction "2_2") (pintype "passive"))
      (node (ref "J4") (pin "1") (pinfunction "1_1") (pintype "passive"))
      (node (ref "QF1") (pin "3") (pinfunction "S_3") (pintype "passive"))
      (node (ref "QF2") (pin "2") (pinfunction "D_2") (pintype "passive"))
      (node (ref "UF1") (pin "6") (pinfunction "VS_6") (pintype "passive"))
    )
    (net (code "9") (name "/NOZZLE1_M2") (class "Default")
      (node (ref "CF9") (pin "1") (pintype "passive"))
      (node (ref "J4") (pin "2") (pinfunction "2_2") (pintype "passive"))
      (node (ref "RF14") (pin "2") (pintype "passive"))
      (node (ref "U3") (pin "1") (pinfunction "RS+_1") (pintype "passive"))
    )
    (net (code "10") (name "/Output") (class "Default")
      (node (ref "RF16") (pin "1") (pintype "passive"))
      (node (ref "RF2") (pin "1") (pintype "passive"))
      (node (ref "RF23") (pin "1") (pintype "passive"))
      (node (ref "RF24") (pin "1") (pintype "passive"))
      (node (ref "U3") (pin "5") (pinfunction "OUT_5") (pintype "passive"))
      (node (ref "UM1") (pin "52") (pinfunction "PTC6/ADC1_SE4/LPUART1_RX/CAN1_RX/FTM3_CH2_52") (pintype "passive"))
    )
    (net (code "11") (name "/PGND") (class "Default")
      (node (ref "C1") (pin "2") (pintype "passive"))
      (node (ref "C2") (pin "2") (pintype "passive"))
      (node (ref "CP10") (pin "2") (pintype "passive"))
      (node (ref "CP11") (pin "2") (pintype "passive"))
      (node (ref "CP12") (pin "2") (pintype "passive"))
      (node (ref "CP13") (pin "2") (pinfunction "2_2") (pintype "passive"))
      (node (ref "CP2") (pin "2") (pintype "passive"))
      (node (ref "CP3") (pin "2") (pintype "passive"))
      (node (ref "CP4") (pin "2") (pintype "passive"))
      (node (ref "CP5") (pin "2") (pintype "passive"))
      (node (ref "CP6") (pin "2") (pintype "passive"))
      (node (ref "CP7") (pin "2") (pintype "passive"))
      (node (ref "CP8") (pin "2") (pintype "passive"))
      (node (ref "DC1") (pin "3") (pinfunction "G_3") (pintype "passive"))
      (node (ref "J2") (pin "2") (pinfunction "2_2") (pintype "passive"))
      (node (ref "J3") (pin "2") (pinfunction "2_2") (pintype "passive"))
      (node (ref "LP3") (pin "1") (pintype "passive"))
      (node (ref "QF2") (pin "3") (pinfunction "S_3") (pintype "passive"))
      (node (ref "QF4") (pin "3") (pinfunction "S_3") (pintype "passive"))
      (node (ref "RP1") (pin "2") (pintype "passive"))
      (node (ref "RPB1") (pin "1") (pintype "passive"))
      (node (ref "UF1") (pin "4") (pinfunction "COM_4") (pintype "passive"))
      (node (ref "UF2") (pin "4") (pinfunction "COM_4") (pintype "passive"))
      (node (ref "UP1") (pin "0") (pinfunction "PAD_0") (pintype "passive"))
      (node (ref "UP1") (pin "10") (pinfunction "AGND_10") (pintype "passive"))
      (node (ref "UP1") (pin "15") (pinfunction "PGND_15") (pintype "passive"))
      (node (ref "UP1") (pin "16") (pinfunction "PGND_16") (pintype "passive"))
      (node (ref "UP1") (pin "6") (pinfunction "SYNC_6") (pintype "passive"))
      (node (ref "UP2") (pin "2") (pinfunction "GND_2") (pintype "passive"))
    )
    (net (code "12") (name "/PWR_5V") (class "Default")
      (node (ref "CP4") (pin "1") (pintype "passive"))
      (node (ref "CP6") (pin "1") (pintype "passive"))
      (node (ref "CP7") (pin "1") (pintype "passive"))
      (node (ref "CP8") (pin "1") (pintype "passive"))
      (node (ref "CPF1") (pin "1") (pintype "passive"))
      (node (ref "LP1") (pin "2") (pinfunction "2_2") (pintype "passive"))
      (node (ref "LP2") (pin "1") (pintype "passive"))
      (node (ref "RPT1") (pin "2") (pintype "passive"))
      (node (ref "UP1") (pin "5") (pinfunction "BIAS_5") (pintype "passive"))
    )
    (net (code "13") (name "/RESET") (class "Default")
      (node (ref "CM1") (pin "1") (pintype "passive"))
      (node (ref "JM1") (pin "6") (pinfunction "6_6") (pintype "passive"))
      (node (ref "RM3") (pin "1") (pintype "passive"))
      (node (ref "UM1") (pin "63") (pinfunction "PTA5/~{RESET}_63") (pintype "passive"))
    )
    (net (code "14") (name "/SWD_CLK") (class "Default")
      (node (ref "RM4") (pin "2") (pintype "passive"))
      (node (ref "UM1") (pin "62") (pinfunction "PTC4/JTAG_TCLK/SWD_CLK/FTM1_CH0_62") (pintype "passive"))
    )
    (net (code "15") (name "/SWD_DIO") (class "Default")
      (node (ref "RM5") (pin "2") (pintype "passive"))
      (node (ref "UM1") (pin "64") (pinfunction "PTA4/JTAG_TMS/SWD_DIO_64") (pintype "passive"))
    )
    (net (code "16") (name "/T1") (class "Default")
      (node (ref "U2") (pin "2") (pinfunction "2_2") (pintype "passive"))
      (node (ref "UM1") (pin "18") (pinfunction "PTB5/FTM0_CH5/LPSPI0_PCS1/LPSPI0_PCS0_18") (pintype "passive"))
    )
    (net (code "17") (name "/T1_H") (class "Default")
      (node (ref "P1") (pin "3") (pinfunction "3_3") (pintype "passive"))
      (node (ref "UM1") (pin "26") (pinfunction "PTC0/ADC0_SE8/FTM0_CH0/LPSPI2_SIN/FTM1_CH6_26") (pintype "passive"))
    )
    (net (code "18") (name "/T1_N") (class "Default")
      (node (ref "RF7") (pin "1") (pintype "passive"))
      (node (ref "UM1") (pin "25") (pinfunction "PTC1/ADC0_SE9/FTM0_CH1/LPSPI2_SOUT/FTM1_CH7_25") (pintype "passive"))
    )
    (net (code "19") (name "/T2") (class "Default")
      (node (ref "U2") (pin "5") (pinfunction "5_5") (pintype "passive"))
      (node (ref "UM1") (pin "19") (pinfunction "PTB4/FTM0_CH4/LPSPI0_SOUT_19") (pintype "passive"))
    )
    (net (code "20") (name "/T2_H") (class "Default")
      (node (ref "P2") (pin "3") (pinfunction "3_3") (pintype "passive"))
      (node (ref "UM1") (pin "20") (pinfunction "PTC3/ADC0_SE11/FTM0_CH3/CAN0_TX/LPUART0_TX_20") (pintype "passive"))
    )
    (net (code "21") (name "/T2_N") (class "Default")
      (node (ref "RF13") (pin "1") (pintype "passive"))
      (node (ref "UM1") (pin "21") (pinfunction "PTC2/ADC0_SE10/FTM0_CH2/CAN0_RX/LPUART0_RX_21") (pintype "passive"))
    )
    (net (code "22") (name "/VIinj1S-") (class "Default")
      (node (ref "CF6") (pin "2") (pinfunction "2_2") (pintype "passive"))
      (node (ref "CF9") (pin "2") (pintype "passive"))
      (node (ref "QF3") (pin "3") (pinfunction "S_3") (pintype "passive"))
      (node (ref "QF4") (pin "2") (pinfunction "D_2") (pintype "passive"))
      (node (ref "RF14") (pin "1") (pintype "passive"))
      (node (ref "U3") (pin "2") (pinfunction "RS-_2") (pintype "passive"))
      (node (ref "UF2") (pin "6") (pinfunction "VS_6") (pintype "passive"))
    )
    (net (code "23") (name "/XTAL") (class "Default")
      (node (ref "CM6") (pin "1") (pintype "passive"))
      (node (ref "RM6") (pin "1") (pintype "passive"))
      (node (ref "UM1") (pin "12") (pinfunction "PTB6/XTAL_12") (pintype "passive"))
      (node (ref "YM1") (pin "3") (pinfunction "3_3") (pintype "passive"))
    )
    (net (code "24") (name "2.5V") (class "Default")
      (node (ref "CS1") (pin "1") (pintype "passive"))
      (node (ref "RF20") (pin "2") (pintype "passive"))
      (node (ref "RS1") (pin "1") (pintype "passive"))
      (node (ref "RS2") (pin "2") (pintype "passive"))
      (node (ref "U3") (pin "7") (pinfunction "REFIN_7") (pintype "passive"))
    )
    (net (code "25") (name "GND") (class "Default")
      (node (ref "CC1") (pin "2") (pintype "passive"))
      (node (ref "CC2") (pin "2") (pintype "passive"))
      (node (ref "CC3") (pin "2") (pintype "passive"))
      (node (ref "CF1") (pin "1") (pintype "passive"))
      (node (ref "CF2") (pin "2") (pintype "passive"))
      (node (ref "CF4") (pin "1") (pintype "passive"))
      (node (ref "CF5") (pin "1") (pintype "passive"))
      (node (ref "CF7") (pin "2") (pintype "passive"))
      (node (ref "CF8") (pin "2") (pintype "passive"))
      (node (ref "CM1") (pin "2") (pintype "passive"))
      (node (ref "CM2") (pin "2") (pintype "passive"))
      (node (ref "CM3") (pin "2") (pintype "passive"))
      (node (ref "CM4") (pin "2") (pintype "passive"))
      (node (ref "CM5") (pin "2") (pintype "passive"))
      (node (ref "CM6") (pin "2") (pintype "passive"))
      (node (ref "CP9") (pin "2") (pintype "passive"))
      (node (ref "CS1") (pin "2") (pintype "passive"))
      (node (ref "JM1") (pin "2") (pinfunction "2_2") (pintype "passive"))
      (node (ref "JM1") (pin "3") (pinfunction "3_3") (pintype "passive"))
      (node (ref "LP3") (pin "2") (pintype "passive"))
      (node (ref "RC1") (pin "2") (pintype "passive"))
      (node (ref "RF22") (pin "1") (pintype "passive"))
      (node (ref "RF9") (pin "1") (pintype "passive"))
      (node (ref "RM1") (pin "2") (pintype "passive"))
      (node (ref "RS2") (pin "1") (pintype "passive"))
      (node (ref "U1") (pin "4") (pinfunction "4_4") (pintype "passive"))
      (node (ref "U2") (pin "7") (pinfunction "7_7") (pintype "passive"))
      (node (ref "U3") (pin "3") (pinfunction "SHDN_3") (pintype "passive"))
      (node (ref "U3") (pin "4") (pinfunction "GND_4") (pintype "passive"))
      (node (ref "UC1") (pin "2") (pinfunction "GND_2") (pintype "passive"))
      (node (ref "UM1") (pin "10") (pinfunction "VSS1_10") (pintype "passive"))
      (node (ref "UM1") (pin "40") (pinfunction "VSS2_40") (pintype "passive"))
      (node (ref "YM1") (pin "2") (pinfunction "2_2") (pintype "passive"))
      (node (ref "YM1") (pin "4") (pinfunction "4_4") (pintype "passive"))
    )
    (net (code "26") (name "Net-(CC3-Pad1)") (class "Default")
      (node (ref "CC3") (pin "1") (pintype "passive"))
      (node (ref "RC2") (pin "1") (pintype "passive"))
      (node (ref "RC3") (pin "1") (pintype "passive"))
    )
    (net (code "27") (name "Net-(CP1-Pad2)") (class "Default")
      (node (ref "CP1") (pin "2") (pintype "passive"))
      (node (ref "LP1") (pin "1") (pinfunction "1_1") (pintype "passive"))
      (node (ref "UP1") (pin "1") (pinfunction "SW_1") (pintype "passive"))
      (node (ref "UP1") (pin "2") (pinfunction "SW_2") (pintype "passive"))
    )
    (net (code "28") (name "Net-(JM1-Pad4)") (class "Default")
      (node (ref "JM1") (pin "4") (pinfunction "4_4") (pintype "passive"))
      (node (ref "RM1") (pin "1") (pintype "passive"))
      (node (ref "RM4") (pin "1") (pintype "passive"))
    )
    (net (code "29") (name "Net-(JM1-Pad5)") (class "Default")
      (node (ref "JM1") (pin "5") (pinfunction "5_5") (pintype "passive"))
      (node (ref "RM2") (pin "1") (pintype "passive"))
      (node (ref "RM5") (pin "1") (pintype "passive"))
    )
    (net (code "30") (name "Net-(P1-Pad1)") (class "Default")
      (node (ref "P1") (pin "1") (pinfunction "1_1") (pintype "passive"))
      (node (ref "RF3") (pin "1") (pintype "passive"))
    )
    (net (code "31") (name "Net-(P1-Pad2)") (class "Default")
      (node (ref "P1") (pin "2") (pinfunction "2_2") (pintype "passive"))
      (node (ref "U2") (pin "3") (pinfunction "3_3") (pintype "passive"))
    )
    (net (code "32") (name "Net-(P2-Pad1)") (class "Default")
      (node (ref "P2") (pin "1") (pinfunction "1_1") (pintype "passive"))
      (node (ref "RF11") (pin "1") (pintype "passive"))
    )
    (net (code "33") (name "Net-(P2-Pad2)") (class "Default")
      (node (ref "P2") (pin "2") (pinfunction "2_2") (pintype "passive"))
      (node (ref "U2") (pin "6") (pinfunction "6_6") (pintype "passive"))
    )
    (net (code "34") (name "Net-(QF1-Pad1)") (class "Default")
      (node (ref "QF1") (pin "1") (pinfunction "1_1") (pintype "passive"))
      (node (ref "RF5") (pin "2") (pintype "passive"))
    )
    (net (code "35") (name "Net-(QF2-Pad1)") (class "Default")
      (node (ref "QF2") (pin "1") (pinfunction "1_1") (pintype "passive"))
      (node (ref "RF8") (pin "2") (pintype "passive"))
    )
    (net (code "36") (name "Net-(QF3-Pad1)") (class "Default")
      (node (ref "QF3") (pin "1") (pinfunction "1_1") (pintype "passive"))
      (node (ref "RF12") (pin "2") (pintype "passive"))
    )
    (net (code "37") (name "Net-(QF4-Pad1)") (class "Default")
      (node (ref "QF4") (pin "1") (pinfunction "1_1") (pintype "passive"))
      (node (ref "RF17") (pin "2") (pintype "passive"))
    )
    (net (code "38") (name "Net-(RF1-Pad2)") (class "Default")
      (node (ref "RF1") (pin "2") (pintype "passive"))
      (node (ref "RF10") (pin "2") (pintype "passive"))
      (node (ref "U1") (pin "1") (pinfunction "1_1") (pintype "passive"))
      (node (ref "U2") (pin "1") (pinfunction "1_1") (pintype "passive"))
    )
    (net (code "39") (name "Net-(RF4-Pad1)") (class "Default")
      (node (ref "RF4") (pin "1") (pintype "passive"))
      (node (ref "RF6") (pin "1") (pintype "passive"))
      (node (ref "RF9") (pin "2") (pintype "passive"))
    )
    (net (code "40") (name "Net-(RF15-Pad1)") (class "Default")
      (node (ref "RF15") (pin "1") (pintype "passive"))
      (node (ref "RF21") (pin "2") (pintype "passive"))
      (node (ref "U1") (pin "7") (pinfunction "7_7") (pintype "passive"))
      (node (ref "U2") (pin "4") (pinfunction "4_4") (pintype "passive"))
    )
    (net (code "41") (name "Net-(RF18-Pad1)") (class "Default")
      (node (ref "RF18") (pin "1") (pintype "passive"))
      (node (ref "RF19") (pin "1") (pintype "passive"))
      (node (ref "RF22") (pin "2") (pintype "passive"))
    )
    (net (code "42") (name "Net-(U1A-+)") (class "Default")
      (node (ref "RF10") (pin "1") (pintype "passive"))
      (node (ref "RF6") (pin "2") (pintype "passive"))
      (node (ref "U1") (pin "3") (pinfunction "+_3") (pintype "passive"))
    )
    (net (code "43") (name "Net-(U1A--)") (class "Default")
      (node (ref "RF2") (pin "2") (pintype "passive"))
      (node (ref "U1") (pin "2") (pinfunction "-_2") (pintype "passive"))
    )
    (net (code "44") (name "Net-(U1B-+)") (class "Default")
      (node (ref "RF19") (pin "2") (pintype "passive"))
      (node (ref "RF21") (pin "1") (pintype "passive"))
      (node (ref "U1") (pin "5") (pinfunction "+_5") (pintype "passive"))
    )
    (net (code "45") (name "Net-(U1B--)") (class "Default")
      (node (ref "RF16") (pin "2") (pintype "passive"))
      (node (ref "U1") (pin "6") (pinfunction "-_6") (pintype "passive"))
    )
    (net (code "46") (name "Net-(U3-FB)") (class "Default")
      (node (ref "RF20") (pin "1") (pintype "passive"))
      (node (ref "RF23") (pin "2") (pintype "passive"))
      (node (ref "U3") (pin "6") (pinfunction "FB_6") (pintype "passive"))
    )
    (net (code "47") (name "Net-(UC1-CANH)") (class "Default")
      (node (ref "LC1") (pin "1") (pinfunction "1_1") (pintype "passive"))
      (node (ref "UC1") (pin "7") (pinfunction "CANH_7") (pintype "passive"))
    )
    (net (code "48") (name "Net-(UC1-CANL)") (class "Default")
      (node (ref "LC1") (pin "2") (pinfunction "2_2") (pintype "passive"))
      (node (ref "UC1") (pin "6") (pinfunction "CANL_6") (pintype "passive"))
    )
    (net (code "49") (name "Net-(UC1-STB)") (class "Default")
      (node (ref "RC1") (pin "1") (pintype "passive"))
      (node (ref "UC1") (pin "8") (pinfunction "STB_8") (pintype "passive"))
    )
    (net (code "50") (name "Net-(UF1-HIN)") (class "Default")
      (node (ref "RF3") (pin "2") (pintype "passive"))
      (node (ref "UF1") (pin "2") (pinfunction "HIN_2") (pintype "passive"))
    )
    (net (code "51") (name "Net-(UF1-HO)") (class "Default")
      (node (ref "RF5") (pin "1") (pintype "passive"))
      (node (ref "UF1") (pin "7") (pinfunction "HO_7") (pintype "passive"))
    )
    (net (code "52") (name "Net-(UF1-LO)") (class "Default")
      (node (ref "RF8") (pin "1") (pintype "passive"))
      (node (ref "UF1") (pin "5") (pinfunction "LO_5") (pintype "passive"))
    )
    (net (code "53") (name "Net-(UF1-VB)") (class "Default")
      (node (ref "CF3") (pin "1") (pinfunction "1_1") (pintype "passive"))
      (node (ref "DF1") (pin "2") (pinfunction "2_2") (pintype "passive"))
      (node (ref "UF1") (pin "8") (pinfunction "VB_8") (pintype "passive"))
    )
    (net (code "54") (name "Net-(UF1-~{LIN})") (class "Default")
      (node (ref "RF7") (pin "2") (pintype "passive"))
      (node (ref "UF1") (pin "3") (pinfunction "~{LIN}_3") (pintype "passive"))
    )
    (net (code "55") (name "Net-(UF2-HIN)") (class "Default")
      (node (ref "RF11") (pin "2") (pintype "passive"))
      (node (ref "UF2") (pin "2") (pinfunction "HIN_2") (pintype "passive"))
    )
    (net (code "56") (name "Net-(UF2-HO)") (class "Default")
      (node (ref "RF12") (pin "1") (pintype "passive"))
      (node (ref "UF2") (pin "7") (pinfunction "HO_7") (pintype "passive"))
    )
    (net (code "57") (name "Net-(UF2-LO)") (class "Default")
      (node (ref "RF17") (pin "1") (pintype "passive"))
      (node (ref "UF2") (pin "5") (pinfunction "LO_5") (pintype "passive"))
    )
    (net (code "58") (name "Net-(UF2-VB)") (class "Default")
      (node (ref "CF6") (pin "1") (pinfunction "1_1") (pintype "passive"))
      (node (ref "DF2") (pin "2") (pinfunction "2_2") (pintype "passive"))
      (node (ref "UF2") (pin "8") (pinfunction "VB_8") (pintype "passive"))
    )
    (net (code "59") (name "Net-(UF2-~{LIN})") (class "Default")
      (node (ref "RF13") (pin "2") (pintype "passive"))
      (node (ref "UF2") (pin "3") (pinfunction "~{LIN}_3") (pintype "passive"))
    )
    (net (code "60") (name "Net-(UP1-CBOOT)") (class "Default")
      (node (ref "CP1") (pin "1") (pintype "passive"))
      (node (ref "UP1") (pin "3") (pinfunction "CBOOT_3") (pintype "passive"))
    )
    (net (code "61") (name "Net-(UP1-FB)") (class "Default")
      (node (ref "CPF1") (pin "2") (pintype "passive"))
      (node (ref "RPB1") (pin "2") (pintype "passive"))
      (node (ref "RPT1") (pin "1") (pintype "passive"))
      (node (ref "UP1") (pin "9") (pinfunction "FB_9") (pintype "passive"))
    )
    (net (code "62") (name "Net-(UP1-RT)") (class "Default")
      (node (ref "RP1") (pin "1") (pintype "passive"))
      (node (ref "UP1") (pin "7") (pinfunction "RT_7") (pintype "passive"))
    )
    (net (code "63") (name "Net-(UP1-VCC)") (class "Default")
      (node (ref "CP5") (pin "1") (pintype "passive"))
      (node (ref "UP1") (pin "4") (pinfunction "VCC_4") (pintype "passive"))
    )
    (net (code "64") (name "Net-(UP2-IN)") (class "Default")
      (node (ref "CP12") (pin "1") (pintype "passive"))
      (node (ref "DP1") (pin "2") (pinfunction "2_2") (pintype "passive"))
      (node (ref "UP2") (pin "3") (pinfunction "IN_3") (pintype "passive"))
    )
    (net (code "65") (name "VBAT") (class "Default")
      (node (ref "C1") (pin "1") (pintype "passive"))
      (node (ref "C2") (pin "1") (pintype "passive"))
      (node (ref "J2") (pin "1") (pinfunction "1_1") (pintype "passive"))
      (node (ref "QF1") (pin "2") (pinfunction "D_2") (pintype "passive"))
      (node (ref "QF3") (pin "2") (pinfunction "D_2") (pintype "passive"))
    )
    (net (code "66") (name "VCC") (class "Default")
      (node (ref "CC1") (pin "1") (pintype "passive"))
      (node (ref "CC2") (pin "1") (pintype "passive"))
      (node (ref "CF1") (pin "2") (pintype "passive"))
      (node (ref "CF2") (pin "1") (pintype "passive"))
      (node (ref "CF4") (pin "2") (pintype "passive"))
      (node (ref "CF5") (pin "2") (pintype "passive"))
      (node (ref "CF7") (pin "1") (pintype "passive"))
      (node (ref "CF8") (pin "1") (pintype "passive"))
      (node (ref "CM2") (pin "1") (pintype "passive"))
      (node (ref "CM3") (pin "1") (pintype "passive"))
      (node (ref "CM4") (pin "1") (pintype "passive"))
      (node (ref "CP9") (pin "1") (pintype "passive"))
      (node (ref "JM1") (pin "1") (pinfunction "1_1") (pintype "passive"))
      (node (ref "LP2") (pin "2") (pintype "passive"))
      (node (ref "RF1") (pin "1") (pintype "passive"))
      (node (ref "RF15") (pin "2") (pintype "passive"))
      (node (ref "RF18") (pin "2") (pintype "passive"))
      (node (ref "RF24") (pin "2") (pintype "passive"))
      (node (ref "RF4") (pin "2") (pintype "passive"))
      (node (ref "RM2") (pin "2") (pintype "passive"))
      (node (ref "RM3") (pin "2") (pintype "passive"))
      (node (ref "RS1") (pin "2") (pintype "passive"))
      (node (ref "U1") (pin "8") (pinfunction "8_8") (pintype "passive"))
      (node (ref "U2") (pin "14") (pinfunction "14_14") (pintype "passive"))
      (node (ref "U3") (pin "8") (pinfunction "VCC_8") (pintype "passive"))
      (node (ref "UC1") (pin "3") (pinfunction "Vcc_3") (pintype "passive"))
      (node (ref "UC1") (pin "5") (pinfunction "Vio_5") (pintype "passive"))
      (node (ref "UM1") (pin "41") (pinfunction "VDD2_41") (pintype "passive"))
      (node (ref "UM1") (pin "7") (pinfunction "VDD1_7") (pintype "passive"))
      (node (ref "UM1") (pin "8") (pinfunction "VDDA_8") (pintype "passive"))
      (node (ref "UM1") (pin "9") (pinfunction "VREFH_9") (pintype "passive"))
    )
    (net (code "67") (name "unconnected-(P1-Pad4)") (class "Default")
      (node (ref "P1") (pin "4") (pinfunction "4_4") (pintype "passive"))
    )
    (net (code "68") (name "unconnected-(P2-Pad4)") (class "Default")
      (node (ref "P2") (pin "4") (pinfunction "4_4") (pintype "passive"))
    )
    (net (code "69") (name "unconnected-(U1-Pad8)") (class "Default")
      (node (ref "U1") (pin "8") (pinfunction "8_8") (pintype "passive"))
    )
    (net (code "70") (name "unconnected-(UM1-PTA0{slash}ADC0_SE0{slash}FTM2_CH1{slash}LPUART0_CTS-Pad50)") (class "Default")
      (node (ref "UM1") (pin "50") (pinfunction "PTA0/ADC0_SE0/FTM2_CH1/LPUART0_CTS_50") (pintype "passive+no_connect"))
    )
    (net (code "71") (name "unconnected-(UM1-PTA1{slash}ADC0_SE1{slash}FTM1_CH1{slash}LPUART0_RTS-Pad49)") (class "Default")
      (node (ref "UM1") (pin "49") (pinfunction "PTA1/ADC0_SE1/FTM1_CH1/LPUART0_RTS_49") (pintype "passive+no_connect"))
    )
    (net (code "72") (name "unconnected-(UM1-PTA2{slash}ADC1_SE0{slash}FTM3_CH0{slash}LPUART0_RX-Pad48)") (class "Default")
      (node (ref "UM1") (pin "48") (pinfunction "PTA2/ADC1_SE0/FTM3_CH0/LPUART0_RX_48") (pintype "passive+no_connect"))
    )
    (net (code "73") (name "unconnected-(UM1-PTA3{slash}ADC1_SE1{slash}FTM3_CH1{slash}LPUART0_TX-Pad47)") (class "Default")
      (node (ref "UM1") (pin "47") (pinfunction "PTA3/ADC1_SE1/FTM3_CH1/LPUART0_TX_47") (pintype "passive+no_connect"))
    )
    (net (code "74") (name "unconnected-(UM1-PTA6{slash}ADC0_SE2{slash}LPSPI1_PCS1{slash}LPUART1_CTS-Pad38)") (class "Default")
      (node (ref "UM1") (pin "38") (pinfunction "PTA6/ADC0_SE2/LPSPI1_PCS1/LPUART1_CTS_38") (pintype "passive+no_connect"))
    )
    (net (code "75") (name "unconnected-(UM1-PTA7{slash}ADC0_SE3{slash}LPUART1_RTS-Pad37)") (class "Default")
      (node (ref "UM1") (pin "37") (pinfunction "PTA7/ADC0_SE3/LPUART1_RTS_37") (pintype "passive+no_connect"))
    )
    (net (code "76") (name "unconnected-(UM1-PTA10{slash}JTAG_TDO{slash}FTM1_CH4-Pad58)") (class "Default")
      (node (ref "UM1") (pin "58") (pinfunction "PTA10/JTAG_TDO/FTM1_CH4_58") (pintype "passive+no_connect"))
    )
    (net (code "77") (name "unconnected-(UM1-PTA11{slash}FTM1_CH5-Pad57)") (class "Default")
      (node (ref "UM1") (pin "57") (pinfunction "PTA11/FTM1_CH5_57") (pintype "passive+no_connect"))
    )
    (net (code "78") (name "unconnected-(UM1-PTB0{slash}ADC0_SE4{slash}ADC1_SE14{slash}LPUART0_RX{slash}LPSPI0_PCS0{slash}CAN0_RX-Pad34)") (class "Default")
      (node (ref "UM1") (pin "34") (pinfunction "PTB0/ADC0_SE4/ADC1_SE14/LPUART0_RX/LPSPI0_PCS0/CAN0_RX_34") (pintype "passive+no_connect"))
    )
    (net (code "79") (name "unconnected-(UM1-PTB1{slash}ADC0_SE5{slash}ADC1_SE15{slash}LPUART0_TX{slash}CAN0_TX-Pad33)") (class "Default")
      (node (ref "UM1") (pin "33") (pinfunction "PTB1/ADC0_SE5/ADC1_SE15/LPUART0_TX/CAN0_TX_33") (pintype "passive+no_connect"))
    )
    (net (code "80") (name "unconnected-(UM1-PTB2{slash}ADC0_SE6{slash}FTM1_CH0{slash}LPSPI0_SCK-Pad32)") (class "Default")
      (node (ref "UM1") (pin "32") (pinfunction "PTB2/ADC0_SE6/FTM1_CH0/LPSPI0_SCK_32") (pintype "passive+no_connect"))
    )
    (net (code "81") (name "unconnected-(UM1-PTB3{slash}ADC0_SE7{slash}FTM1_CH1{slash}LPSPI0_SIN-Pad31)") (class "Default")
      (node (ref "UM1") (pin "31") (pinfunction "PTB3/ADC0_SE7/FTM1_CH1/LPSPI0_SIN_31") (pintype "passive+no_connect"))
    )
    (net (code "82") (name "unconnected-(UM1-PTB12{slash}ADC1_SE7{slash}FTM0_CH0{slash}CAN2_RX-Pad43)") (class "Default")
      (node (ref "UM1") (pin "43") (pinfunction "PTB12/ADC1_SE7/FTM0_CH0/CAN2_RX_43") (pintype "passive+no_connect"))
    )
    (net (code "83") (name "unconnected-(UM1-PTB13{slash}ADC1_SE8{slash}ADC0_SE8{slash}FTM0_CH1{slash}CAN2_TX-Pad42)") (class "Default")
      (node (ref "UM1") (pin "42") (pinfunction "PTB13/ADC1_SE8/ADC0_SE8/FTM0_CH1/CAN2_TX_42") (pintype "passive+no_connect"))
    )
    (net (code "84") (name "unconnected-(UM1-PTC5{slash}JTAG_TDI{slash}FTM2_CH0-Pad61)") (class "Default")
      (node (ref "UM1") (pin "61") (pinfunction "PTC5/JTAG_TDI/FTM2_CH0_61") (pintype "passive+no_connect"))
    )
    (net (code "85") (name "unconnected-(UM1-PTC7{slash}ADC1_SE5{slash}LPUART1_TX{slash}CAN1_TX{slash}FTM3_CH3-Pad51)") (class "Default")
      (node (ref "UM1") (pin "51") (pinfunction "PTC7/ADC1_SE5/LPUART1_TX/CAN1_TX/FTM3_CH3_51") (pintype "passive+no_connect"))
    )
    (net (code "86") (name "unconnected-(UM1-PTC8{slash}LPUART1_RX-Pad36)") (class "Default")
      (node (ref "UM1") (pin "36") (pinfunction "PTC8/LPUART1_RX_36") (pintype "passive+no_connect"))
    )
    (net (code "87") (name "unconnected-(UM1-PTC9{slash}LPUART1_TX-Pad35)") (class "Default")
      (node (ref "UM1") (pin "35") (pinfunction "PTC9/LPUART1_TX_35") (pintype "passive+no_connect"))
    )
    (net (code "88") (name "unconnected-(UM1-PTC14{slash}ADC0_SE12{slash}FTM1_CH2{slash}LPSPI2_PCS0-Pad30)") (class "Default")
      (node (ref "UM1") (pin "30") (pinfunction "PTC14/ADC0_SE12/FTM1_CH2/LPSPI2_PCS0_30") (pintype "passive"))
    )
    (net (code "89") (name "unconnected-(UM1-PTC15{slash}ADC0_SE13{slash}FTM1_CH3{slash}LPSPI2_SCK-Pad29)") (class "Default")
      (node (ref "UM1") (pin "29") (pinfunction "PTC15/ADC0_SE13/FTM1_CH3/LPSPI2_SCK_29") (pintype "passive"))
    )
    (net (code "90") (name "unconnected-(UM1-PTC16{slash}ADC0_SE14{slash}CAN2_RX-Pad28)") (class "Default")
      (node (ref "UM1") (pin "28") (pinfunction "PTC16/ADC0_SE14/CAN2_RX_28") (pintype "passive+no_connect"))
    )
    (net (code "91") (name "unconnected-(UM1-PTC17{slash}ADC0_SE15{slash}CAN2_TX-Pad27)") (class "Default")
      (node (ref "UM1") (pin "27") (pinfunction "PTC17/ADC0_SE15/CAN2_TX_27") (pintype "passive+no_connect"))
    )
    (net (code "92") (name "unconnected-(UM1-PTD0{slash}FTM0_CH2{slash}LPSPI1_SCK{slash}FTM2_CH0-Pad2)") (class "Default")
      (node (ref "UM1") (pin "2") (pinfunction "PTD0/FTM0_CH2/LPSPI1_SCK/FTM2_CH0_2") (pintype "passive+no_connect"))
    )
    (net (code "93") (name "unconnected-(UM1-PTD1{slash}FTM0_CH3{slash}LPSPI1_SIN{slash}FTM2_CH1-Pad1)") (class "Default")
      (node (ref "UM1") (pin "1") (pinfunction "PTD1/FTM0_CH3/LPSPI1_SIN/FTM2_CH1_1") (pintype "passive+no_connect"))
    )
    (net (code "94") (name "unconnected-(UM1-PTD2{slash}ADC1_SE2{slash}FTM3_CH4{slash}LPSPI1_SOUT-Pad46)") (class "Default")
      (node (ref "UM1") (pin "46") (pinfunction "PTD2/ADC1_SE2/FTM3_CH4/LPSPI1_SOUT_46") (pintype "passive+no_connect"))
    )
    (net (code "95") (name "unconnected-(UM1-PTD3{slash}ADC1_SE3{slash}FTM3_CH5{slash}LPSPI1_PCS0-Pad45)") (class "Default")
      (node (ref "UM1") (pin "45") (pinfunction "PTD3/ADC1_SE3/FTM3_CH5/LPSPI1_PCS0_45") (pintype "passive+no_connect"))
    )
    (net (code "96") (name "unconnected-(UM1-PTD4{slash}ADC1_SE6-Pad44)") (class "Default")
      (node (ref "UM1") (pin "44") (pinfunction "PTD4/ADC1_SE6_44") (pintype "passive+no_connect"))
    )
    (net (code "97") (name "unconnected-(UM1-PTD5{slash}FTM2_CH3-Pad24)") (class "Default")
      (node (ref "UM1") (pin "24") (pinfunction "PTD5/FTM2_CH3_24") (pintype "passive+no_connect"))
    )
    (net (code "98") (name "unconnected-(UM1-PTD6{slash}LPUART2_RX-Pad23)") (class "Default")
      (node (ref "UM1") (pin "23") (pinfunction "PTD6/LPUART2_RX_23") (pintype "passive+no_connect"))
    )
    (net (code "99") (name "unconnected-(UM1-PTD7{slash}LPUART2_TX-Pad22)") (class "Default")
      (node (ref "UM1") (pin "22") (pinfunction "PTD7/LPUART2_TX_22") (pintype "passive+no_connect"))
    )
    (net (code "100") (name "unconnected-(UM1-PTD15{slash}FTM0_CH0{slash}LPSPI0_SCK-Pad15)") (class "Default")
      (node (ref "UM1") (pin "15") (pinfunction "PTD15/FTM0_CH0/LPSPI0_SCK_15") (pintype "passive+no_connect"))
    )
    (net (code "101") (name "unconnected-(UM1-PTD16{slash}FTM0_CH1{slash}LPSPI0_SIN-Pad14)") (class "Default")
      (node (ref "UM1") (pin "14") (pinfunction "PTD16/FTM0_CH1/LPSPI0_SIN_14") (pintype "passive+no_connect"))
    )
    (net (code "102") (name "unconnected-(UM1-PTE0{slash}LPSPI0_SCK{slash}LPSPI1_SOUT-Pad60)") (class "Default")
      (node (ref "UM1") (pin "60") (pinfunction "PTE0/LPSPI0_SCK/LPSPI1_SOUT_60") (pintype "passive+no_connect"))
    )
    (net (code "103") (name "unconnected-(UM1-PTE1{slash}LPSPI0_SIN{slash}LPSPI1_PCS0-Pad59)") (class "Default")
      (node (ref "UM1") (pin "59") (pinfunction "PTE1/LPSPI0_SIN/LPSPI1_PCS0_59") (pintype "passive+no_connect"))
    )
    (net (code "104") (name "unconnected-(UM1-PTE2{slash}ADC1_SE10{slash}LPSPI0_SOUT{slash}FTM3_CH6-Pad54)") (class "Default")
      (node (ref "UM1") (pin "54") (pinfunction "PTE2/ADC1_SE10/LPSPI0_SOUT/FTM3_CH6_54") (pintype "passive+no_connect"))
    )
    (net (code "105") (name "unconnected-(UM1-PTE3-Pad13)") (class "Default")
      (node (ref "UM1") (pin "13") (pinfunction "PTE3_13") (pintype "passive+no_connect"))
    )
    (net (code "106") (name "unconnected-(UM1-PTE4{slash}FTM2_CH2{slash}CAN0_RX-Pad6)") (class "Default")
      (node (ref "UM1") (pin "6") (pinfunction "PTE4/FTM2_CH2/CAN0_RX_6") (pintype "passive+no_connect"))
    )
    (net (code "107") (name "unconnected-(UM1-PTE5{slash}FTM2_CH3{slash}CAN0_TX-Pad5)") (class "Default")
      (node (ref "UM1") (pin "5") (pinfunction "PTE5/FTM2_CH3/CAN0_TX_5") (pintype "passive+no_connect"))
    )
    (net (code "108") (name "unconnected-(UM1-PTE6{slash}ADC1_SE11{slash}LPSPI0_PCS2{slash}FTM3_CH7-Pad53)") (class "Default")
      (node (ref "UM1") (pin "53") (pinfunction "PTE6/ADC1_SE11/LPSPI0_PCS2/FTM3_CH7_53") (pintype "passive+no_connect"))
    )
    (net (code "109") (name "unconnected-(UM1-PTE7{slash}FTM0_CH7-Pad39)") (class "Default")
      (node (ref "UM1") (pin "39") (pinfunction "PTE7/FTM0_CH7_39") (pintype "passive+no_connect"))
    )
    (net (code "110") (name "unconnected-(UM1-PTE8{slash}FTM0_CH6-Pad17)") (class "Default")
      (node (ref "UM1") (pin "17") (pinfunction "PTE8/FTM0_CH6_17") (pintype "passive+no_connect"))
    )
    (net (code "111") (name "unconnected-(UM1-PTE9{slash}FTM0_CH7-Pad16)") (class "Default")
      (node (ref "UM1") (pin "16") (pinfunction "PTE9/FTM0_CH7_16") (pintype "passive+no_connect"))
    )
    (net (code "112") (name "unconnected-(UM1-PTE10{slash}LPSPI2_PCS1{slash}FTM2_CH4-Pad4)") (class "Default")
      (node (ref "UM1") (pin "4") (pinfunction "PTE10/LPSPI2_PCS1/FTM2_CH4_4") (pintype "passive+no_connect"))
    )
    (net (code "113") (name "unconnected-(UM1-PTE11{slash}LPSPI2_PCS0{slash}FTM2_CH5-Pad3)") (class "Default")
      (node (ref "UM1") (pin "3") (pinfunction "PTE11/LPSPI2_PCS0/FTM2_CH5_3") (pintype "passive+no_connect"))
    )
    (net (code "114") (name "unconnected-(UP1-PGOOD-Pad8)") (class "Default")
      (node (ref "UP1") (pin "8") (pinfunction "PGOOD_8") (pintype "passive+no_connect"))
    )
    (net (code "115") (name "unconnected-(UP1-SS-Pad11)") (class "Default")
      (node (ref "UP1") (pin "11") (pinfunction "SS_11") (pintype "passive+no_connect"))
    )
  )
)
